# Memory.net
KiCad netlist of a schematic drawn in Altium Designer
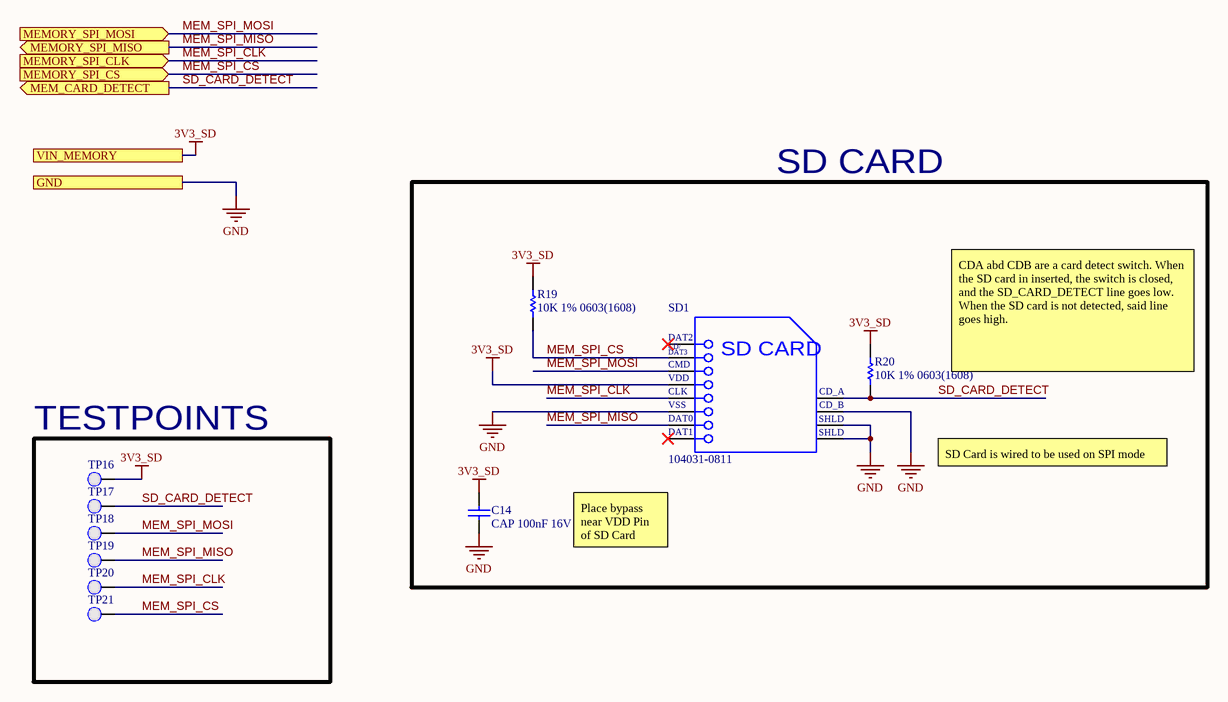
[diagram p0: Memory.SchDoc]

(export (version "E")
  (design (tool "Eeschema 10.0.6"))
  (components
    (comp (ref "C14")
      (value "CAP 100nF 16V 0603(1608)")
      (footprint "CAPC0603(1608)100_N")
      (description "CAP 100nF 16V ±10% 0603 (1608 Metric) Thickness 1mm SMD")
      (fields (field (name "TOLERANCE") "Â±10%"))
      (libsource (lib "Altium Content Vault") (part "CAP"))
    )
    (comp (ref "R19")
      (value "10K 1% 0603(1608)")
      (footprint "RESC0603(1608)_N")
      (description "10K 0.1W 1% 0603 (1608 Metric)  SMD")
      (fields (field (name "POWER") "0.1 W") (field (name "TOLERANCE") "1 %"))
      (libsource (lib "Altium Content Vault") (part "RES"))
    )
    (comp (ref "R20")
      (value "10K 1% 0603(1608)")
      (footprint "RESC0603(1608)_N")
      (description "10K 0.1W 1% 0603 (1608 Metric)  SMD")
      (fields (field (name "POWER") "0.1 W") (field (name "TOLERANCE") "1 %"))
      (libsource (lib "Altium Content Vault") (part "RES"))
    )
    (comp (ref "SD1")
      (value "104031-0811")
      (footprint "MOLX-104031-0811_V")
      (description "Micro SD Card, RA, -25 to 85 degC, 8-Pin SMD, RoHS, Tape and Reel")
      (fields (field (name "MANUFACTURER") "Molex"))
      (libsource (lib "Altium Content Vault") (part "CN-SD-8-2SW-2S"))
    )
    (comp (ref "TP16")
      (value "0.1\" Pad")
      (footprint "PCBComponent")
      (libsource (lib "Components - 12.02.20 - 18.05") (part "0.1{dblquote} Pad-A.4"))
    )
    (comp (ref "TP17")
      (value "0.1\" Pad")
      (footprint "PCBComponent")
      (libsource (lib "Components - 12.02.20 - 18.05") (part "0.1{dblquote} Pad-A.4"))
    )
    (comp (ref "TP18")
      (value "0.1\" Pad")
      (footprint "PCBComponent")
      (libsource (lib "Components - 12.02.20 - 18.05") (part "0.1{dblquote} Pad-A.4"))
    )
    (comp (ref "TP19")
      (value "0.1\" Pad")
      (footprint "PCBComponent")
      (libsource (lib "Components - 12.02.20 - 18.05") (part "0.1{dblquote} Pad-A.4"))
    )
    (comp (ref "TP20")
      (value "0.1\" Pad")
      (footprint "PCBComponent")
      (libsource (lib "Components - 12.02.20 - 18.05") (part "0.1{dblquote} Pad-A.4"))
    )
    (comp (ref "TP21")
      (value "0.1\" Pad")
      (footprint "PCBComponent")
      (libsource (lib "Components - 12.02.20 - 18.05") (part "0.1{dblquote} Pad-A.4"))
    )
  )
  (nets
    (net (code "1") (name "/MEM_SPI_CLK") (class "Default")
      (node (ref "SD1") (pin "5") (pinfunction "CLK_5") (pintype "passive"))
      (node (ref "TP20") (pin "1") (pinfunction "PAD_1") (pintype "passive"))
    )
    (net (code "2") (name "/MEM_SPI_CS") (class "Default")
      (node (ref "R19") (pin "1") (pinfunction "1_1") (pintype "passive"))
      (node (ref "SD1") (pin "2") (pinfunction "CMD_2") (pintype "passive"))
      (node (ref "TP21") (pin "1") (pinfunction "PAD_1") (pintype "passive"))
    )
    (net (code "3") (name "/MEM_SPI_MISO") (class "Default")
      (node (ref "SD1") (pin "7") (pinfunction "DAT0_7") (pintype "passive"))
      (node (ref "TP19") (pin "1") (pinfunction "PAD_1") (pintype "passive"))
    )
    (net (code "4") (name "/MEM_SPI_MOSI") (class "Default")
      (node (ref "SD1") (pin "3") (pinfunction "VSS1_3") (pintype "passive"))
      (node (ref "TP18") (pin "1") (pinfunction "PAD_1") (pintype "passive"))
    )
    (net (code "5") (name "/SD_CARD_DETECT") (class "Default")
      (node (ref "R20") (pin "1") (pinfunction "1_1") (pintype "passive"))
      (node (ref "SD1") (pin "9") (pinfunction "CD_A_9") (pintype "passive"))
      (node (ref "TP17") (pin "1") (pinfunction "PAD_1") (pintype "passive"))
    )
    (net (code "6") (name "3V3_SD") (class "Default")
      (node (ref "C14") (pin "2") (pinfunction "2_2") (pintype "passive"))
      (node (ref "R19") (pin "2") (pinfunction "2_2") (pintype "passive"))
      (node (ref "R20") (pin "2") (pinfunction "2_2") (pintype "passive"))
      (node (ref "SD1") (pin "4") (pinfunction "VDD_4") (pintype "passive"))
      (node (ref "TP16") (pin "1") (pinfunction "PAD_1") (pintype "passive"))
    )
    (net (code "7") (name "GND") (class "Default")
      (node (ref "C14") (pin "1") (pinfunction "1_1") (pintype "passive"))
      (node (ref "SD1") (pin "10") (pinfunction "CD_B_10") (pintype "passive"))
      (node (ref "SD1") (pin "11") (pinfunction "SHLD1_11") (pintype "passive"))
      (node (ref "SD1") (pin "12") (pinfunction "SHLD2_12") (pintype "passive"))
      (node (ref "SD1") (pin "6") (pinfunction "VSS2_6") (pintype "passive"))
    )
    (net (code "8") (name "unconnected-(SD1-CD{slash}DAT3-Pad1)") (class "Default")
      (node (ref "SD1") (pin "1") (pinfunction "CD/DAT3_1") (pintype "passive+no_connect"))
    )
    (net (code "9") (name "unconnected-(SD1-DAT1-Pad8)") (class "Default")
      (node (ref "SD1") (pin "8") (pinfunction "DAT1_8") (pintype "passive+no_connect"))
    )
  )
)
